# RF.net
KiCad netlist of a schematic drawn in Altium Designer
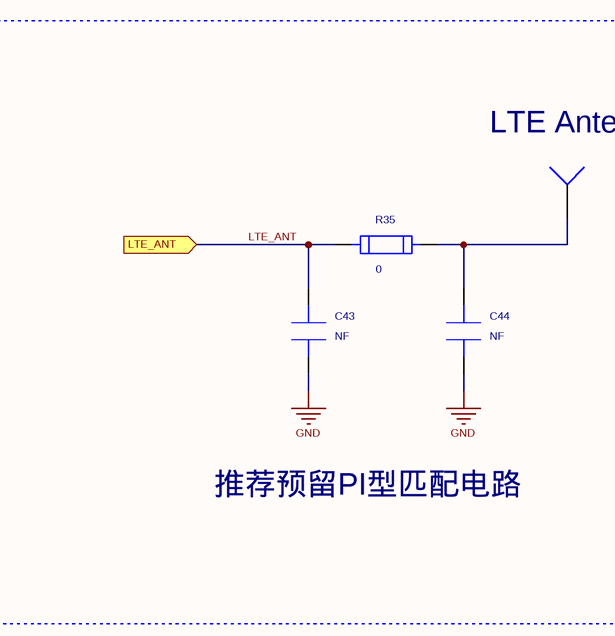
[diagram p0: RF.SchDoc, top left]
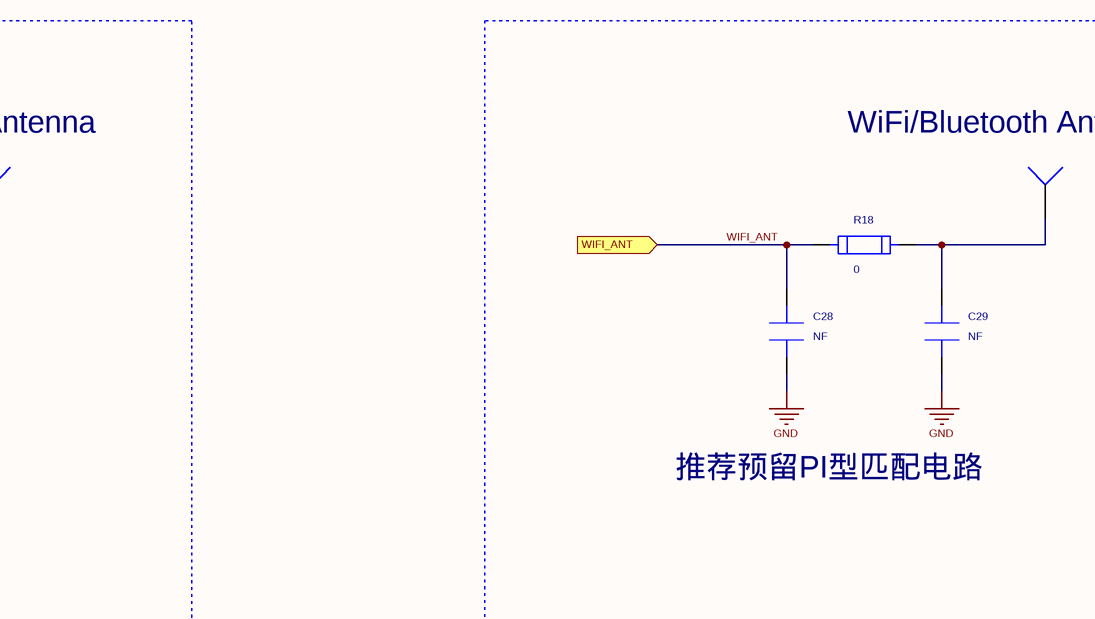
[diagram p1: RF.SchDoc, top middle]
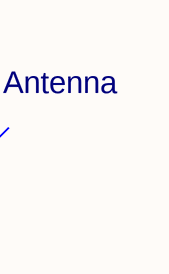
[diagram p2: RF.SchDoc, top right]
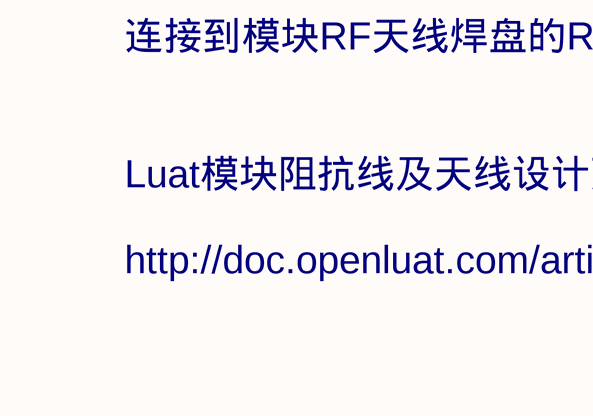
[diagram p3: RF.SchDoc, bottom left]
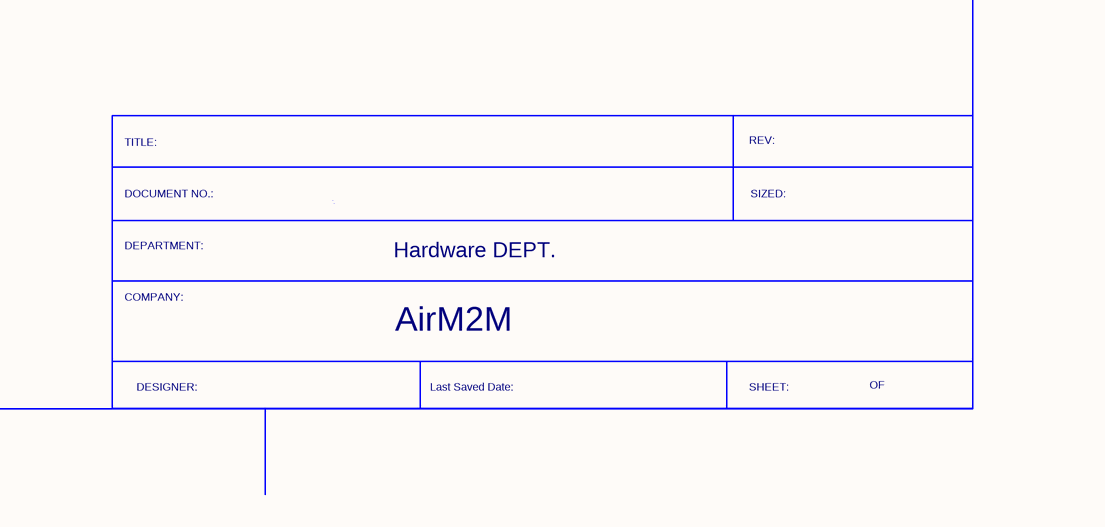
[diagram p4: RF.SchDoc, bottom right]

(export (version "E")
  (design (tool "Eeschema 10.0.6"))
  (components
    (comp (ref "C28")
      (value "NF")
      (footprint "SC0402-NF")
      (fields (field (name "Comment") "CAP-0402-NF"))
      (libsource (lib "*") (part "CAP-0402-NF"))
    )
    (comp (ref "C29")
      (value "NF")
      (footprint "SC0402-NF")
      (fields (field (name "Comment") "CAP-0402-NF"))
      (libsource (lib "*") (part "CAP-0402-NF"))
    )
    (comp (ref "C43")
      (value "NF")
      (footprint "SC0402-NF")
      (fields (field (name "Comment") "CAP-0402-NF"))
      (libsource (lib "*") (part "CAP-0402-NF"))
    )
    (comp (ref "C44")
      (value "NF")
      (footprint "SC0402-NF")
      (fields (field (name "Comment") "CAP-0402-NF"))
      (libsource (lib "*") (part "CAP-0402-NF"))
    )
    (comp (ref "J1")
      (value "RF-ANT-P-JS-29-13")
      (footprint "RF-ANT-P-JS-29-13")
      (description "天线馈点连接器;1PIN;2.91*1.0*1.3mm;ROHS")
      (libsource (lib "*") (part "RF-ANT-P-JS-29-13"))
    )
    (comp (ref "J6")
      (value "RF-ANT-P-JS-29-13")
      (footprint "RF-ANT-P-JS-29-13")
      (description "天线馈点连接器;1PIN;2.91*1.0*1.3mm;ROHS")
      (libsource (lib "*") (part "RF-ANT-P-JS-29-13"))
    )
    (comp (ref "R18")
      (value "0")
      (footprint "SR0402")
      (description "RES FILM;0;1A;0402;0.4mm;ROHS")
      (fields (field (name "Comment") "RES-0-0402"))
      (libsource (lib "*") (part "RES-0-0402"))
    )
    (comp (ref "R35")
      (value "0")
      (footprint "SR0402")
      (description "RES FILM;0;1A;0402;0.4mm;ROHS")
      (fields (field (name "Comment") "RES-0-0402"))
      (libsource (lib "*") (part "RES-0-0402"))
    )
  )
  (nets
    (net (code "1") (name "/LTE_ANT") (class "Default")
      (node (ref "C43") (pin "1") (pinfunction "1_1") (pintype "passive"))
      (node (ref "R35") (pin "1") (pinfunction "1_1") (pintype "passive"))
    )
    (net (code "2") (name "/WIFI_ANT") (class "Default")
      (node (ref "C28") (pin "1") (pinfunction "1_1") (pintype "passive"))
      (node (ref "R18") (pin "1") (pinfunction "1_1") (pintype "passive"))
    )
    (net (code "3") (name "GND") (class "Default")
      (node (ref "C28") (pin "2") (pinfunction "2_2") (pintype "passive"))
      (node (ref "C29") (pin "2") (pinfunction "2_2") (pintype "passive"))
      (node (ref "C43") (pin "2") (pinfunction "2_2") (pintype "passive"))
      (node (ref "C44") (pin "2") (pinfunction "2_2") (pintype "passive"))
    )
    (net (code "4") (name "Net-(C29-Pad1)") (class "Default")
      (node (ref "C29") (pin "1") (pinfunction "1_1") (pintype "passive"))
      (node (ref "J1") (pin "1") (pinfunction "1_1") (pintype "passive"))
      (node (ref "R18") (pin "2") (pinfunction "2_2") (pintype "passive"))
    )
    (net (code "5") (name "Net-(C44-Pad1)") (class "Default")
      (node (ref "C44") (pin "1") (pinfunction "1_1") (pintype "passive"))
      (node (ref "J6") (pin "1") (pinfunction "1_1") (pintype "passive"))
      (node (ref "R35") (pin "2") (pinfunction "2_2") (pintype "passive"))
    )
  )
)
